# RPi_MCU.net
KiCad netlist of a schematic drawn in Altium Designer
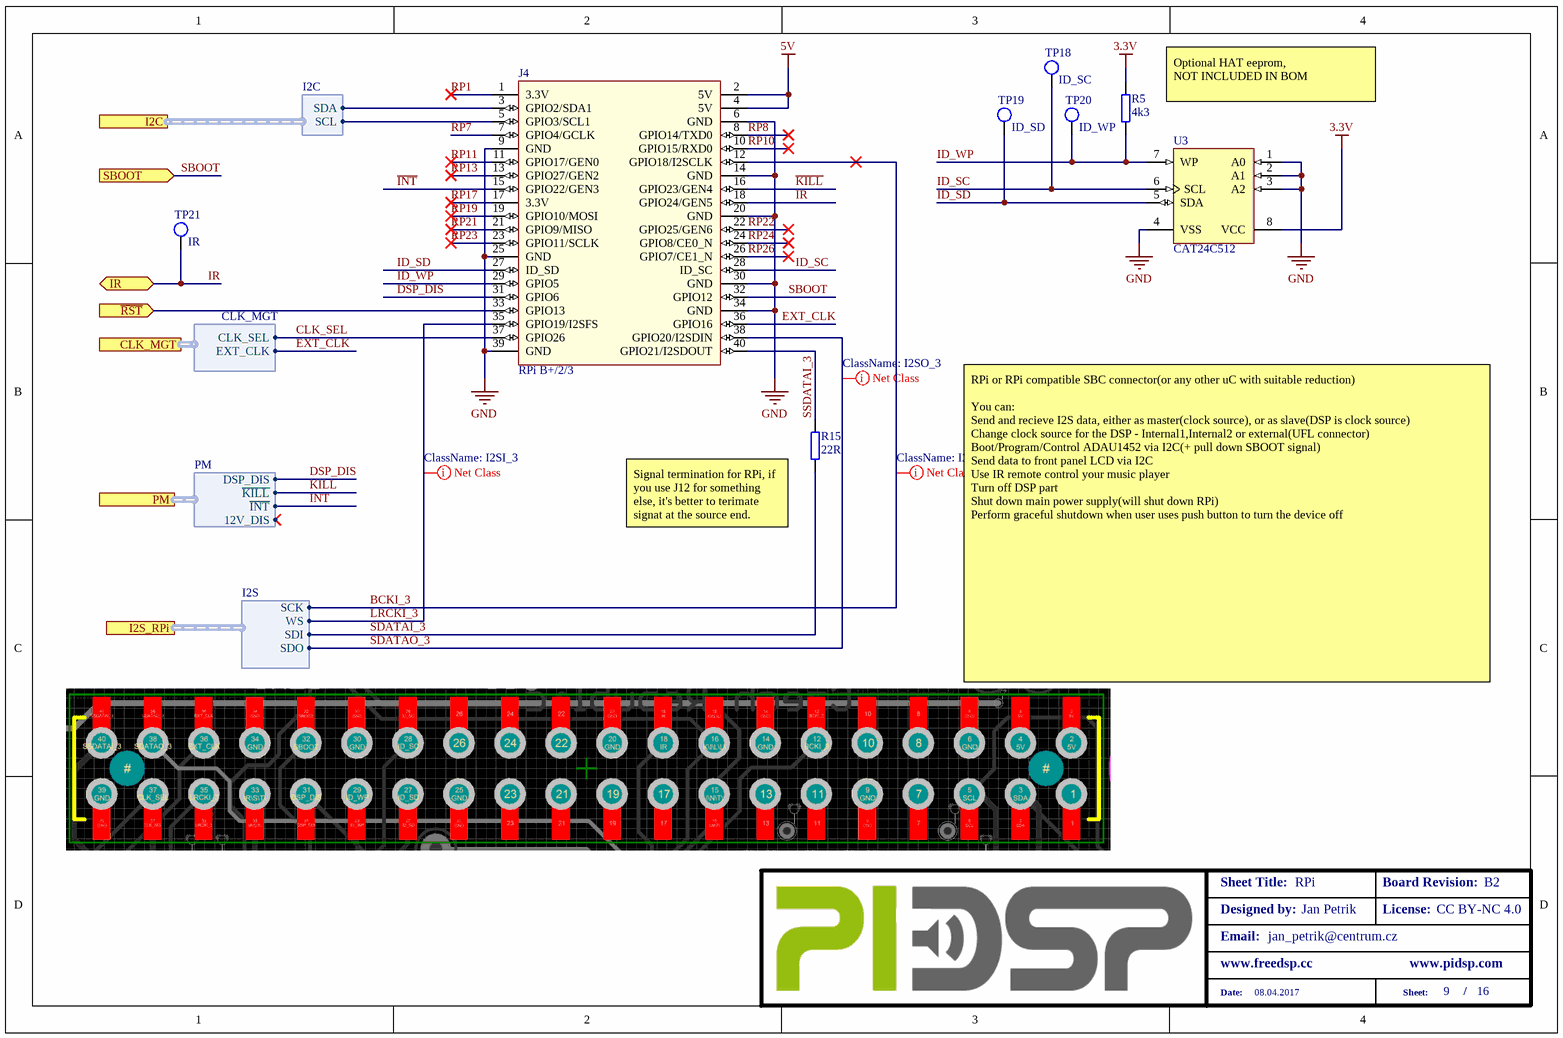
[diagram p0: RPi&MCU.SchDoc]

(export (version "E")
  (design (tool "Eeschema 10.0.6"))
  (components
    (comp (ref "J4")
      (value "RPi B+/2/3")
      (footprint "RPi 2")
      (description "Rapsberry Pi Header")
      (libsource (lib "JP_IC") (part "Rapsberry Pi 2 B"))
    )
    (comp (ref "R5")
      (value "4k3")
      (footprint "RESC1608X06N(SMR0603)")
      (description "Chip Resistor")
      (fields (field (name "AUTHOR") "JP/10.06.2014"))
      (libsource (lib "JP_R") (part "4K3-100mW-0603-ThickFilm"))
    )
    (comp (ref "R15")
      (value "22R")
      (footprint "RESC1608X06N(SMR0603)")
      (description "Chip Resistor")
      (fields (field (name "AUTHOR") "JP/10.06.2014"))
      (libsource (lib "JP_R") (part "22R-100mW-0603-ThickFilm"))
    )
    (comp (ref "TP18")
      (value "ID_SC")
      (footprint "TP_0.8/0.4_ROUND")
      (description "Testpoint - VIA")
      (libsource (lib "JP_CONN") (part "TEST_POINT_VIA"))
    )
    (comp (ref "TP19")
      (value "ID_SD")
      (footprint "TP_0.8/0.4_ROUND")
      (description "Testpoint - VIA")
      (libsource (lib "JP_CONN") (part "TEST_POINT_VIA"))
    )
    (comp (ref "TP20")
      (value "ID_WP")
      (footprint "TP_0.8/0.4_ROUND")
      (description "Testpoint - VIA")
      (libsource (lib "JP_CONN") (part "TEST_POINT_VIA"))
    )
    (comp (ref "TP21")
      (value "IR")
      (footprint "TP_0.8/0.4_ROUND")
      (description "Testpoint - VIA")
      (libsource (lib "JP_CONN") (part "TEST_POINT_VIA"))
    )
    (comp (ref "U3")
      (value "CAT24C512")
      (footprint "SOIC127P600X175-8N(SOIC_8)")
      (description "512 Kb I2C CMOS Serial  EEPROM")
      (libsource (lib "JP_IC") (part "CAT24C512"))
    )
  )
  (nets
    (net (code "5") (name "/BCKI_3") (class "Default")
      (node (ref "J4") (pin "12") (pinfunction "GPIO18/I2SCLK_12") (pintype "bidirectional"))
    )
    (net (code "6") (name "/CLK_SEL") (class "Default")
      (node (ref "J4") (pin "37") (pinfunction "GPIO26_37") (pintype "bidirectional"))
    )
    (net (code "7") (name "/DSP_DIS") (class "Default")
      (node (ref "J4") (pin "31") (pinfunction "GPIO6_31") (pintype "bidirectional"))
    )
    (net (code "8") (name "/EXT_CLK") (class "Default")
      (node (ref "J4") (pin "36") (pinfunction "GPIO16_36") (pintype "bidirectional"))
    )
    (net (code "9") (name "/ID_SC") (class "Default")
      (node (ref "J4") (pin "28") (pinfunction "ID_SC_28") (pintype "bidirectional"))
      (node (ref "TP18") (pin "1") (pintype "passive"))
      (node (ref "U3") (pin "6") (pinfunction "SCL_6") (pintype "input"))
    )
    (net (code "10") (name "/ID_SD") (class "Default")
      (node (ref "J4") (pin "27") (pinfunction "ID_SD_27") (pintype "bidirectional"))
      (node (ref "TP19") (pin "1") (pintype "passive"))
      (node (ref "U3") (pin "5") (pinfunction "SDA_5") (pintype "bidirectional"))
    )
    (net (code "11") (name "/ID_WP") (class "Default")
      (node (ref "J4") (pin "29") (pinfunction "GPIO5_29") (pintype "bidirectional"))
      (node (ref "R5") (pin "1") (pinfunction "1_1") (pintype "passive"))
      (node (ref "TP20") (pin "1") (pintype "passive"))
      (node (ref "U3") (pin "7") (pinfunction "WP_7") (pintype "input"))
    )
    (net (code "12") (name "/IR") (class "Default")
      (node (ref "J4") (pin "18") (pinfunction "GPIO24/GEN5_18") (pintype "bidirectional"))
      (node (ref "TP21") (pin "1") (pintype "passive"))
    )
    (net (code "13") (name "/LRCKI_3") (class "Default")
      (node (ref "J4") (pin "35") (pinfunction "GPIO19/I2SFS_35") (pintype "bidirectional"))
    )
    (net (code "14") (name "/RP1") (class "Default")
      (node (ref "J4") (pin "1") (pinfunction "3.3V_1") (pintype "power_in+no_connect"))
    )
    (net (code "15") (name "/RP7") (class "Default")
      (node (ref "J4") (pin "7") (pinfunction "GPIO4/GCLK_7") (pintype "bidirectional"))
    )
    (net (code "16") (name "/RP8") (class "Default")
      (node (ref "J4") (pin "8") (pinfunction "GPIO14/TXD0_8") (pintype "bidirectional+no_connect"))
    )
    (net (code "17") (name "/RP10") (class "Default")
      (node (ref "J4") (pin "10") (pinfunction "GPIO15/RXD0_10") (pintype "bidirectional+no_connect"))
    )
    (net (code "18") (name "/RP11") (class "Default")
      (node (ref "J4") (pin "11") (pinfunction "GPIO17/GEN0_11") (pintype "bidirectional+no_connect"))
    )
    (net (code "19") (name "/RP13") (class "Default")
      (node (ref "J4") (pin "13") (pinfunction "GPIO27/GEN2_13") (pintype "bidirectional+no_connect"))
    )
    (net (code "20") (name "/RP17") (class "Default")
      (node (ref "J4") (pin "17") (pinfunction "3.3V_17") (pintype "power_in+no_connect"))
    )
    (net (code "21") (name "/RP19") (class "Default")
      (node (ref "J4") (pin "19") (pinfunction "GPIO10/MOSI_19") (pintype "bidirectional+no_connect"))
    )
    (net (code "22") (name "/RP21") (class "Default")
      (node (ref "J4") (pin "21") (pinfunction "GPIO9/MISO_21") (pintype "bidirectional+no_connect"))
    )
    (net (code "23") (name "/RP22") (class "Default")
      (node (ref "J4") (pin "22") (pinfunction "GPIO25/GEN6_22") (pintype "bidirectional+no_connect"))
    )
    (net (code "24") (name "/RP23") (class "Default")
      (node (ref "J4") (pin "23") (pinfunction "GPIO11/SCLK_23") (pintype "bidirectional+no_connect"))
    )
    (net (code "25") (name "/RP24") (class "Default")
      (node (ref "J4") (pin "24") (pinfunction "GPIO8/CE0_N_24") (pintype "bidirectional+no_connect"))
    )
    (net (code "26") (name "/RP26") (class "Default")
      (node (ref "J4") (pin "26") (pinfunction "GPIO7/CE1_N_26") (pintype "bidirectional+no_connect"))
    )
    (net (code "27") (name "/SBOOT") (class "Default")
      (node (ref "J4") (pin "32") (pinfunction "GPIO12_32") (pintype "bidirectional"))
    )
    (net (code "28") (name "/SCL") (class "Default")
      (node (ref "J4") (pin "5") (pinfunction "GPIO3/SCL1_5") (pintype "bidirectional"))
    )
    (net (code "29") (name "/SDA") (class "Default")
      (node (ref "J4") (pin "3") (pinfunction "GPIO2/SDA1_3") (pintype "bidirectional"))
    )
    (net (code "30") (name "/SDATAI_3") (class "Default")
      (node (ref "R15") (pin "1") (pinfunction "1_1") (pintype "passive"))
    )
    (net (code "31") (name "/SDATAO_3") (class "Default")
      (node (ref "J4") (pin "38") (pinfunction "GPIO20/I2SDIN_38") (pintype "bidirectional"))
    )
    (net (code "32") (name "/SSDATAI_3") (class "Default")
      (node (ref "J4") (pin "40") (pinfunction "GPIO21/I2SDOUT_40") (pintype "bidirectional"))
      (node (ref "R15") (pin "2") (pinfunction "2_2") (pintype "passive"))
    )
    (net (code "37") (name "/~{INT}") (class "Default")
      (node (ref "J4") (pin "15") (pinfunction "GPIO22/GEN3_15") (pintype "bidirectional"))
    )
    (net (code "38") (name "/~{KILL}") (class "Default")
      (node (ref "J4") (pin "16") (pinfunction "GPIO23/GEN4_16") (pintype "bidirectional"))
    )
    (net (code "39") (name "/~{RST}") (class "Default")
      (node (ref "J4") (pin "33") (pinfunction "GPIO13_33") (pintype "bidirectional"))
    )
    (net (code "40") (name "3.3V") (class "Default")
      (node (ref "R5") (pin "2") (pinfunction "2_2") (pintype "passive"))
      (node (ref "U3") (pin "8") (pinfunction "VCC_8") (pintype "power_in"))
    )
    (net (code "41") (name "5V") (class "Default")
      (node (ref "J4") (pin "2") (pinfunction "5V_2") (pintype "power_in"))
      (node (ref "J4") (pin "4") (pinfunction "5V_4") (pintype "power_in"))
    )
    (net (code "42") (name "GND") (class "Default")
      (node (ref "J4") (pin "14") (pinfunction "GND_14") (pintype "power_in"))
      (node (ref "J4") (pin "20") (pinfunction "GND_20") (pintype "power_in"))
      (node (ref "J4") (pin "25") (pinfunction "GND_25") (pintype "power_in"))
      (node (ref "J4") (pin "30") (pinfunction "GND_30") (pintype "power_in"))
      (node (ref "J4") (pin "34") (pinfunction "GND_34") (pintype "power_in"))
      (node (ref "J4") (pin "39") (pinfunction "GND_39") (pintype "power_in"))
      (node (ref "J4") (pin "6") (pinfunction "GND_6") (pintype "power_in"))
      (node (ref "J4") (pin "9") (pinfunction "GND_9") (pintype "power_in"))
      (node (ref "U3") (pin "1") (pinfunction "A0_1") (pintype "input"))
      (node (ref "U3") (pin "2") (pinfunction "A1_2") (pintype "input"))
      (node (ref "U3") (pin "3") (pinfunction "A2_3") (pintype "input"))
      (node (ref "U3") (pin "4") (pinfunction "VSS_4") (pintype "power_in"))
    )
  )
)
